# Fence.net
KiCad netlist of a schematic drawn in EAGLE
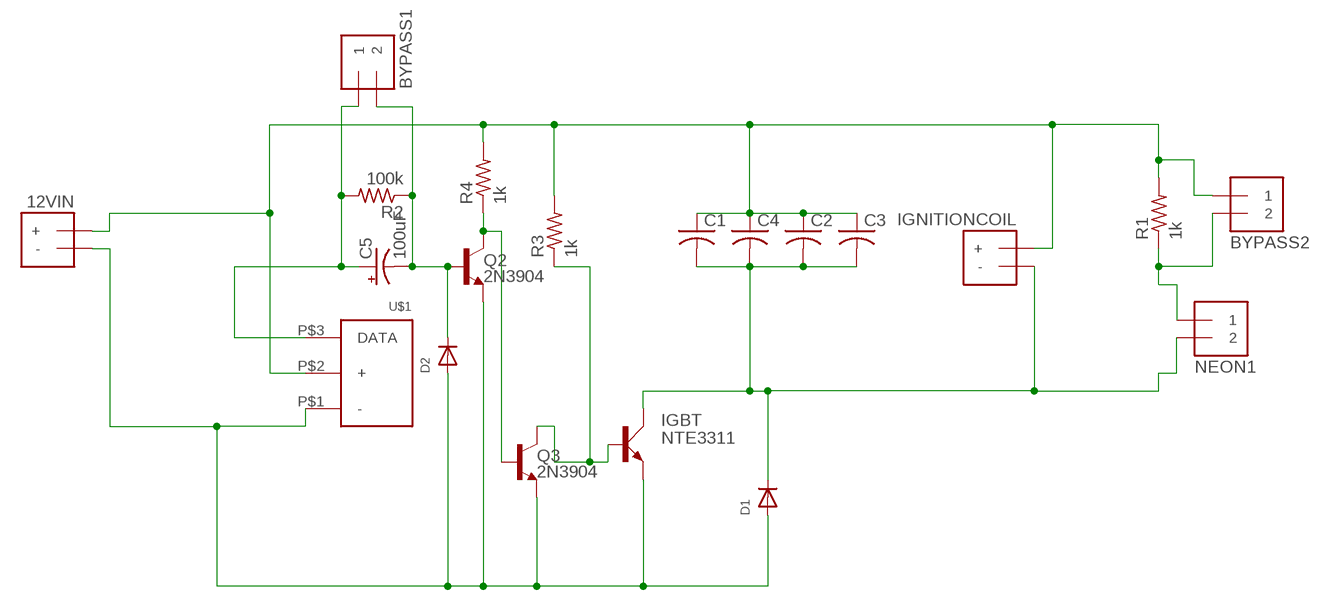
[diagram p0: schematic, sheet 1]

(export (version "E")
  (design (tool "Eeschema 10.0.6"))
  (components
    (comp (ref "12VIN")
      (value "1X2_-++-")
      (footprint "eagle-import:1X2_+-")
      (libsource (lib "eagle-import") (part "1X2_-++-"))
    )
    (comp (ref "BYPASS1")
      (value "1X2_12PINS")
      (footprint "eagle-import:1X2PINS")
      (libsource (lib "eagle-import") (part "1X2_12PINS"))
    )
    (comp (ref "BYPASS2")
      (value "1X2_12PINS")
      (footprint "eagle-import:1X2PINS")
      (libsource (lib "eagle-import") (part "1X2_12PINS"))
    )
    (comp (ref "C1")
      (value "C-US225-062X268")
      (footprint "eagle-import:C225-062X268")
      (libsource (lib "eagle-import") (part "C-US225-062X268"))
    )
    (comp (ref "C2")
      (value "C-US225-062X268")
      (footprint "eagle-import:C225-062X268")
      (libsource (lib "eagle-import") (part "C-US225-062X268"))
    )
    (comp (ref "C3")
      (value "C-US225-062X268")
      (footprint "eagle-import:C225-062X268")
      (libsource (lib "eagle-import") (part "C-US225-062X268"))
    )
    (comp (ref "C4")
      (value "C-US225-062X268")
      (footprint "eagle-import:C225-062X268")
      (libsource (lib "eagle-import") (part "C-US225-062X268"))
    )
    (comp (ref "C5")
      (value "100uF")
      (footprint "eagle-import:E2,5-5")
      (libsource (lib "eagle-import") (part "CPOL-USE2.5-5"))
    )
    (comp (ref "D1")
      (value "DIODEDO-1N4148")
      (footprint "eagle-import:DO-1N4148")
      (libsource (lib "eagle-import") (part "DIODEDO-1N4148"))
    )
    (comp (ref "D2")
      (value "DIODEDO-1N4148")
      (footprint "eagle-import:DO-1N4148")
      (libsource (lib "eagle-import") (part "DIODEDO-1N4148"))
    )
    (comp (ref "IGBT")
      (value "NTE3311")
      (footprint "eagle-import:TOP3AV")
      (libsource (lib "eagle-import") (part "TIP3055"))
    )
    (comp (ref "IGNITIONCOIL")
      (value "1X2_-++-")
      (footprint "eagle-import:1X2_+-")
      (libsource (lib "eagle-import") (part "1X2_-++-"))
    )
    (comp (ref "NEON1")
      (value "Neon Lamp")
      (footprint "eagle-import:1X2_12")
      (libsource (lib "eagle-import") (part "1X2_1212"))
    )
    (comp (ref "Q2")
      (value "2N3904")
      (footprint "eagle-import:TO-92INSERT")
      (libsource (lib "eagle-import") (part "TRANS_NPN"))
    )
    (comp (ref "Q3")
      (value "2N3904")
      (footprint "eagle-import:TO-92INSERT")
      (libsource (lib "eagle-import") (part "TRANS_NPN"))
    )
    (comp (ref "R1")
      (value "1k")
      (footprint "eagle-import:0204_7")
      (libsource (lib "eagle-import") (part "R-US_0204/7"))
    )
    (comp (ref "R2")
      (value "100k")
      (footprint "eagle-import:0207_10")
      (libsource (lib "eagle-import") (part "R-US_0207/10"))
    )
    (comp (ref "R3")
      (value "1k")
      (footprint "eagle-import:0207_12")
      (libsource (lib "eagle-import") (part "R-US_0207/12"))
    )
    (comp (ref "R4")
      (value "1k")
      (footprint "eagle-import:0207_12")
      (libsource (lib "eagle-import") (part "R-US_0207/12"))
    )
    (comp (ref "U$1")
      (value "SERVO")
      (footprint "eagle-import:1X3")
      (libsource (lib "eagle-import") (part "SERVO"))
    )
  )
  (nets
    (net (code "1") (name "Net-(BYPASS2-Pad2)") (class "Default")
      (node (ref "BYPASS2") (pin "2") (pinfunction "2_2") (pintype "passive"))
      (node (ref "NEON1") (pin "1") (pinfunction "1_1") (pintype "passive"))
      (node (ref "R1") (pin "1") (pinfunction "1_1") (pintype "passive"))
    )
    (net (code "2") (name "Net-(C1-Pad2)") (class "Default")
      (node (ref "C1") (pin "2") (pinfunction "2_2") (pintype "passive"))
      (node (ref "C2") (pin "2") (pinfunction "2_2") (pintype "passive"))
      (node (ref "C3") (pin "2") (pinfunction "2_2") (pintype "passive"))
      (node (ref "C4") (pin "2") (pinfunction "2_2") (pintype "passive"))
      (node (ref "D1") (pin "C") (pinfunction "C_C") (pintype "passive"))
      (node (ref "IGBT") (pin "C") (pinfunction "C_C") (pintype "passive"))
      (node (ref "IGNITIONCOIL") (pin "-") (pinfunction "-_-") (pintype "passive"))
      (node (ref "NEON1") (pin "2") (pinfunction "2_2") (pintype "passive"))
    )
    (net (code "3") (name "Net-(Q2-B)") (class "Default")
      (node (ref "BYPASS1") (pin "2") (pinfunction "2_2") (pintype "passive"))
      (node (ref "C5") (pin "-") (pinfunction "-_-") (pintype "passive"))
      (node (ref "D2") (pin "C") (pinfunction "C_C") (pintype "passive"))
      (node (ref "Q2") (pin "2") (pinfunction "B_2") (pintype "passive"))
      (node (ref "R2") (pin "1") (pinfunction "1_1") (pintype "passive"))
    )
    (net (code "4") (name "Net-(Q2-C)") (class "Default")
      (node (ref "Q2") (pin "1") (pinfunction "C_1") (pintype "passive"))
      (node (ref "Q3") (pin "2") (pinfunction "B_2") (pintype "passive"))
      (node (ref "R4") (pin "1") (pinfunction "1_1") (pintype "passive"))
    )
    (net (code "5") (name "Net-(Q2-E)") (class "Default")
      (node (ref "12VIN") (pin "-") (pinfunction "-_-") (pintype "passive"))
      (node (ref "D1") (pin "A") (pinfunction "A_A") (pintype "passive"))
      (node (ref "D2") (pin "A") (pinfunction "A_A") (pintype "passive"))
      (node (ref "IGBT") (pin "E") (pinfunction "E_E") (pintype "passive"))
      (node (ref "Q2") (pin "3") (pinfunction "E_3") (pintype "passive"))
      (node (ref "Q3") (pin "3") (pinfunction "E_3") (pintype "passive"))
      (node (ref "U$1") (pin "P$1") (pinfunction "-_P$1") (pintype "bidirectional"))
    )
    (net (code "6") (name "Net-(Q3-C)") (class "Default")
      (node (ref "IGBT") (pin "B") (pinfunction "B_B") (pintype "passive"))
      (node (ref "Q3") (pin "1") (pinfunction "C_1") (pintype "passive"))
      (node (ref "R3") (pin "1") (pinfunction "1_1") (pintype "passive"))
    )
    (net (code "7") (name "Net-(U$1-+)") (class "Default")
      (node (ref "12VIN") (pin "+") (pinfunction "+_+") (pintype "passive"))
      (node (ref "BYPASS2") (pin "1") (pinfunction "1_1") (pintype "passive"))
      (node (ref "C1") (pin "1") (pinfunction "1_1") (pintype "passive"))
      (node (ref "C2") (pin "1") (pinfunction "1_1") (pintype "passive"))
      (node (ref "C3") (pin "1") (pinfunction "1_1") (pintype "passive"))
      (node (ref "C4") (pin "1") (pinfunction "1_1") (pintype "passive"))
      (node (ref "IGNITIONCOIL") (pin "+") (pinfunction "+_+") (pintype "passive"))
      (node (ref "R1") (pin "2") (pinfunction "2_2") (pintype "passive"))
      (node (ref "R3") (pin "2") (pinfunction "2_2") (pintype "passive"))
      (node (ref "R4") (pin "2") (pinfunction "2_2") (pintype "passive"))
      (node (ref "U$1") (pin "P$2") (pinfunction "+_P$2") (pintype "bidirectional"))
    )
    (net (code "8") (name "Net-(U$1-DATA)") (class "Default")
      (node (ref "BYPASS1") (pin "1") (pinfunction "1_1") (pintype "passive"))
      (node (ref "C5") (pin "+") (pinfunction "+_+") (pintype "passive"))
      (node (ref "R2") (pin "2") (pinfunction "2_2") (pintype "passive"))
      (node (ref "U$1") (pin "P$3") (pinfunction "DATA_P$3") (pintype "bidirectional"))
    )
  )
)
